# low_voltage_output_controller.net
KiCad netlist of a schematic drawn in Altium Designer
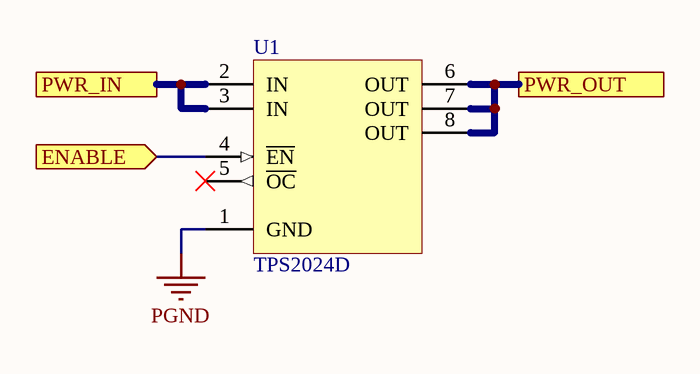
[diagram p0: low voltage output controller.SchDoc]

(export (version "E")
  (design (tool "Eeschema 10.0.6"))
  (components
    (comp (ref "U1")
      (value "TPS2024D")
      (footprint "TPS2024D")
      (description "TEXAS INSTRUMENTS - TPS2024D - IC, 3A PWR DIST SWITCH 8-SOIC")
      (libsource (lib "TPS2024D") (part "TPS2024D"))
    )
  )
  (nets
    (net (code "1") (name "/ENABLE") (class "Default")
      (node (ref "U1") (pin "4") (pinfunction "~{EN}_4") (pintype "input"))
    )
    (net (code "2") (name "/PWR_IN") (class "Default")
      (node (ref "U1") (pin "2") (pinfunction "IN_2") (pintype "power_in"))
      (node (ref "U1") (pin "3") (pinfunction "IN_3") (pintype "power_in"))
    )
    (net (code "3") (name "/PWR_OUT") (class "Default")
      (node (ref "U1") (pin "6") (pinfunction "OUT_6") (pintype "passive"))
      (node (ref "U1") (pin "7") (pinfunction "OUT_7") (pintype "passive"))
      (node (ref "U1") (pin "8") (pinfunction "OUT_8") (pintype "passive"))
    )
    (net (code "4") (name "PGND") (class "Default")
      (node (ref "U1") (pin "1") (pinfunction "GND_1") (pintype "power_in"))
    )
    (net (code "5") (name "unconnected-(U1-~{OC}-Pad5)") (class "Default")
      (node (ref "U1") (pin "5") (pinfunction "~{OC}_5") (pintype "output+no_connect"))
    )
  )
)
